# STeaMi-FP11-Port_JTAG.net
KiCad netlist of a schematic drawn in Altium Designer
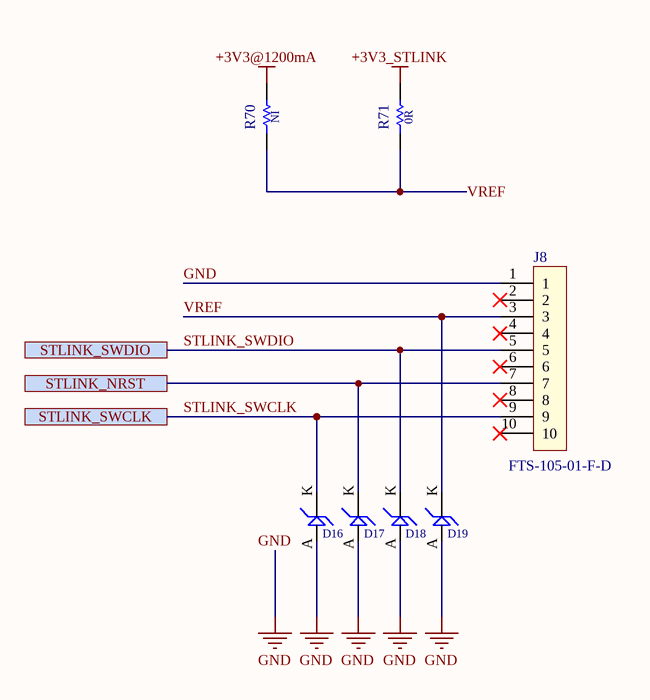
[diagram p0: STeaMi-FP11-Port_JTAG.SchDoc]

(export (version "E")
  (design (tool "Eeschema 10.0.6"))
  (components
    (comp (ref "D16")
      (value "~")
      (footprint "SODFL1608X70N")
      (description "Suppresseurs ESD / diodes TVS LOW CAP SNAPBACK ESD PROT")
      (fields
        (field (name "MANUFACTURER") "OnSemiconductor")
        (field (name "MANUFACTURER PART NUMBER") "ESD8351XV2T1G")
        (field (name "CREATED BY") "EAG")
      )
      (libsource (lib "ComponentDB") (part "DIODE_ZENER_SYMBOL"))
    )
    (comp (ref "D17")
      (value "~")
      (footprint "SODFL1608X70N")
      (description "Suppresseurs ESD / diodes TVS LOW CAP SNAPBACK ESD PROT")
      (fields
        (field (name "MANUFACTURER") "OnSemiconductor")
        (field (name "MANUFACTURER PART NUMBER") "ESD8351XV2T1G")
        (field (name "CREATED BY") "EAG")
      )
      (libsource (lib "ComponentDB") (part "DIODE_ZENER_SYMBOL"))
    )
    (comp (ref "D18")
      (value "~")
      (footprint "SODFL1608X70N")
      (description "Suppresseurs ESD / diodes TVS LOW CAP SNAPBACK ESD PROT")
      (fields
        (field (name "MANUFACTURER") "OnSemiconductor")
        (field (name "MANUFACTURER PART NUMBER") "ESD8351XV2T1G")
        (field (name "CREATED BY") "EAG")
      )
      (libsource (lib "ComponentDB") (part "DIODE_ZENER_SYMBOL"))
    )
    (comp (ref "D19")
      (value "~")
      (footprint "SODFL1608X70N")
      (description "Suppresseurs ESD / diodes TVS LOW CAP SNAPBACK ESD PROT")
      (fields
        (field (name "MANUFACTURER") "OnSemiconductor")
        (field (name "MANUFACTURER PART NUMBER") "ESD8351XV2T1G")
        (field (name "CREATED BY") "EAG")
      )
      (libsource (lib "ComponentDB") (part "DIODE_ZENER_SYMBOL"))
    )
    (comp (ref "J8")
      (value "~")
      (footprint "FTS-105-01-F-D")
      (description "Embase FTS 10 point 1,27 mm vertical")
      (fields
        (field (name "MANUFACTURER") "SAMTEC")
        (field (name "MANUFACTURER PART NUMBER") "FTS-105-01-F-D")
        (field (name "PART NUMBER") "FTS-105-01-F-D")
        (field (name "CHECKED BY") "*")
        (field (name "CREATED BY") "EAG")
      )
      (libsource (lib "ComponentDB") (part "FTS-105-01-F-D"))
    )
    (comp (ref "R70")
      (value "~")
      (footprint "RESC1005X40N_0402")
      (description "NI")
      (fields
        (field (name "POWER") "0,1")
        (field (name "RESISTANCE") "NI")
        (field (name "PART NUMBER") "NI-1%-0,1W-0603")
        (field (name "CREATED BY") "MSA")
      )
      (libsource (lib "ComponentDB") (part "RES_SYMBOL"))
    )
    (comp (ref "R71")
      (value "~")
      (footprint "RESC1005X40N_0402")
      (description "RES CMS 0R5%-0,0625W-0402")
      (fields
        (field (name "MANUFACTURER") "Yageo")
        (field (name "MANUFACTURER PART NUMBER") "RC0402JR-100RL")
        (field (name "RESISTANCE") "0R")
        (field (name "CREATED BY") "EAG")
      )
      (libsource (lib "ComponentDB") (part "RES_SYMBOL"))
    )
  )
  (nets
    (net (code "1") (name "+3V3@1200mA") (class "Default")
      (node (ref "R70") (pin "2") (pinfunction "2_2") (pintype "passive"))
    )
    (net (code "2") (name "+3V3_STLINK") (class "Default")
      (node (ref "R71") (pin "2") (pinfunction "2_2") (pintype "passive"))
    )
    (net (code "3") (name "/STLINK_NRST") (class "Default")
      (node (ref "D17") (pin "K") (pinfunction "K_K") (pintype "passive"))
      (node (ref "J8") (pin "7") (pinfunction "7_7") (pintype "passive"))
    )
    (net (code "4") (name "/STLINK_SWCLK") (class "Default")
      (node (ref "D16") (pin "K") (pinfunction "K_K") (pintype "passive"))
      (node (ref "J8") (pin "9") (pinfunction "9_9") (pintype "passive"))
    )
    (net (code "5") (name "/STLINK_SWDIO") (class "Default")
      (node (ref "D18") (pin "K") (pinfunction "K_K") (pintype "passive"))
      (node (ref "J8") (pin "5") (pinfunction "5_5") (pintype "passive"))
    )
    (net (code "6") (name "/VREF") (class "Default")
      (node (ref "D19") (pin "K") (pinfunction "K_K") (pintype "passive"))
      (node (ref "J8") (pin "3") (pinfunction "3_3") (pintype "passive"))
      (node (ref "R70") (pin "1") (pinfunction "1_1") (pintype "passive"))
      (node (ref "R71") (pin "1") (pinfunction "1_1") (pintype "passive"))
    )
    (net (code "7") (name "GND") (class "Default")
      (node (ref "D16") (pin "A") (pinfunction "A_A") (pintype "passive"))
      (node (ref "D17") (pin "A") (pinfunction "A_A") (pintype "passive"))
      (node (ref "D18") (pin "A") (pinfunction "A_A") (pintype "passive"))
      (node (ref "D19") (pin "A") (pinfunction "A_A") (pintype "passive"))
      (node (ref "J8") (pin "1") (pinfunction "1_1") (pintype "passive"))
    )
    (net (code "8") (name "unconnected-(J8-Pad2)") (class "Default")
      (node (ref "J8") (pin "2") (pinfunction "2_2") (pintype "passive+no_connect"))
    )
    (net (code "9") (name "unconnected-(J8-Pad4)") (class "Default")
      (node (ref "J8") (pin "4") (pinfunction "4_4") (pintype "passive+no_connect"))
    )
    (net (code "10") (name "unconnected-(J8-Pad6)") (class "Default")
      (node (ref "J8") (pin "6") (pinfunction "6_6") (pintype "passive+no_connect"))
    )
    (net (code "11") (name "unconnected-(J8-Pad8)") (class "Default")
      (node (ref "J8") (pin "8") (pinfunction "8_8") (pintype "passive+no_connect"))
    )
    (net (code "12") (name "unconnected-(J8-Pad10)") (class "Default")
      (node (ref "J8") (pin "10") (pinfunction "10_10") (pintype "passive+no_connect"))
    )
  )
)
